# FPC_CAP_Water_Level.net
KiCad netlist of a schematic drawn in Altium Designer
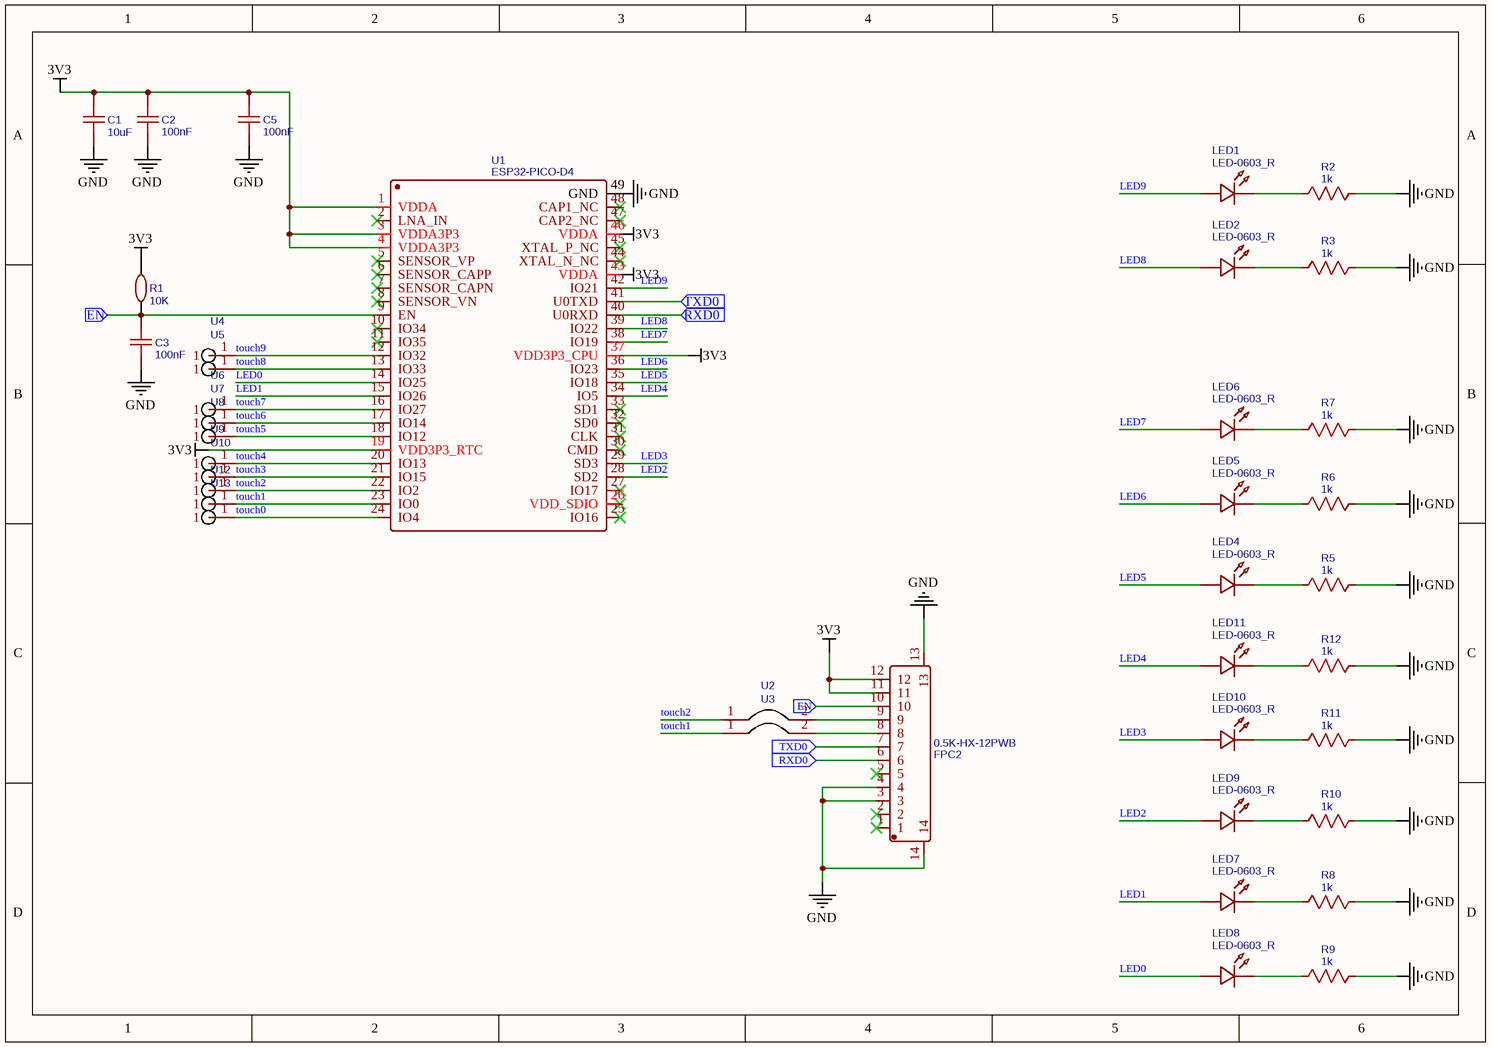
[diagram p0: FPC_CAP_Water_Level.schdoc]

(export (version "E")
  (design (tool "Eeschema 10.0.6"))
  (components
    (comp (ref "C1")
      (value "10uF")
      (footprint "C0603")
      (fields (field (name "MANUFACTURER") "SAMSUNG") (field (name "MANUFACTURER PART") "CL10A106MP8NNNC"))
      (libsource (lib "altium-import") (part "root_1_10uF_"))
    )
    (comp (ref "C2")
      (value "100nF")
      (footprint "C0603")
      (fields (field (name "MANUFACTURER") "SAMSUNG") (field (name "MANUFACTURER PART") "CL10B104KB8NNNC"))
      (libsource (lib "altium-import") (part "root_1_100nF_"))
    )
    (comp (ref "C3")
      (value "100nF")
      (footprint "C0603")
      (fields (field (name "MANUFACTURER") "SAMSUNG") (field (name "MANUFACTURER PART") "CL10B104KB8NNNC"))
      (libsource (lib "altium-import") (part "root_1_100nF_"))
    )
    (comp (ref "C5")
      (value "100nF")
      (footprint "C0603")
      (fields (field (name "MANUFACTURER") "SAMSUNG") (field (name "MANUFACTURER PART") "CL10B104KB8NNNC"))
      (libsource (lib "altium-import") (part "root_1_100nF_"))
    )
    (comp (ref "FPC2")
      (value "0.5K-HX-12PWB")
      (footprint "FPC-SMD_12P-P0.50_HDGC_0.5K-HX-12PWB")
      (fields (field (name "MANUFACTURER") "HDGC(华德共创)") (field (name "CONTRIBUTOR") "LCSC"))
      (libsource (lib "altium-import") (part "root_0_0.5K-HX-12PWB_"))
    )
    (comp (ref "LED1")
      (value "LED-0603_R")
      (footprint "LED0603_RED")
      (fields
        (field (name "MANUFACTURER") "EVERLIGHT(台湾亿光)")
        (field (name "MANUFACTURER PART") "19-217/R6C-AL1M2VY/3T")
        (field (name "CONTRIBUTOR") "LCEDA_01")
      )
      (libsource (lib "altium-import") (part "root_0_LED-0603_R_"))
    )
    (comp (ref "LED2")
      (value "LED-0603_R")
      (footprint "LED0603_RED")
      (fields
        (field (name "MANUFACTURER") "EVERLIGHT(台湾亿光)")
        (field (name "MANUFACTURER PART") "19-217/R6C-AL1M2VY/3T")
        (field (name "CONTRIBUTOR") "LCEDA_01")
      )
      (libsource (lib "altium-import") (part "root_0_LED-0603_R_"))
    )
    (comp (ref "LED4")
      (value "LED-0603_R")
      (footprint "LED0603_RED")
      (fields
        (field (name "MANUFACTURER") "EVERLIGHT(台湾亿光)")
        (field (name "MANUFACTURER PART") "19-217/R6C-AL1M2VY/3T")
        (field (name "CONTRIBUTOR") "LCEDA_01")
      )
      (libsource (lib "altium-import") (part "root_0_LED-0603_R_"))
    )
    (comp (ref "LED5")
      (value "LED-0603_R")
      (footprint "LED0603_RED")
      (fields
        (field (name "MANUFACTURER") "EVERLIGHT(台湾亿光)")
        (field (name "MANUFACTURER PART") "19-217/R6C-AL1M2VY/3T")
        (field (name "CONTRIBUTOR") "LCEDA_01")
      )
      (libsource (lib "altium-import") (part "root_0_LED-0603_R_"))
    )
    (comp (ref "LED6")
      (value "LED-0603_R")
      (footprint "LED0603_RED")
      (fields
        (field (name "MANUFACTURER") "EVERLIGHT(台湾亿光)")
        (field (name "MANUFACTURER PART") "19-217/R6C-AL1M2VY/3T")
        (field (name "CONTRIBUTOR") "LCEDA_01")
      )
      (libsource (lib "altium-import") (part "root_0_LED-0603_R_"))
    )
    (comp (ref "LED7")
      (value "LED-0603_R")
      (footprint "LED0603_RED")
      (fields
        (field (name "MANUFACTURER") "EVERLIGHT(台湾亿光)")
        (field (name "MANUFACTURER PART") "19-217/R6C-AL1M2VY/3T")
        (field (name "CONTRIBUTOR") "LCEDA_01")
      )
      (libsource (lib "altium-import") (part "root_0_LED-0603_R_"))
    )
    (comp (ref "LED8")
      (value "LED-0603_R")
      (footprint "LED0603_RED")
      (fields
        (field (name "MANUFACTURER") "EVERLIGHT(台湾亿光)")
        (field (name "MANUFACTURER PART") "19-217/R6C-AL1M2VY/3T")
        (field (name "CONTRIBUTOR") "LCEDA_01")
      )
      (libsource (lib "altium-import") (part "root_0_LED-0603_R_"))
    )
    (comp (ref "LED9")
      (value "LED-0603_R")
      (footprint "LED0603_RED")
      (fields
        (field (name "MANUFACTURER") "EVERLIGHT(台湾亿光)")
        (field (name "MANUFACTURER PART") "19-217/R6C-AL1M2VY/3T")
        (field (name "CONTRIBUTOR") "LCEDA_01")
      )
      (libsource (lib "altium-import") (part "root_0_LED-0603_R_"))
    )
    (comp (ref "LED10")
      (value "LED-0603_R")
      (footprint "LED0603_RED")
      (fields
        (field (name "MANUFACTURER") "EVERLIGHT(台湾亿光)")
        (field (name "MANUFACTURER PART") "19-217/R6C-AL1M2VY/3T")
        (field (name "CONTRIBUTOR") "LCEDA_01")
      )
      (libsource (lib "altium-import") (part "root_0_LED-0603_R_"))
    )
    (comp (ref "LED11")
      (value "LED-0603_R")
      (footprint "LED0603_RED")
      (fields
        (field (name "MANUFACTURER") "EVERLIGHT(台湾亿光)")
        (field (name "MANUFACTURER PART") "19-217/R6C-AL1M2VY/3T")
        (field (name "CONTRIBUTOR") "LCEDA_01")
      )
      (libsource (lib "altium-import") (part "root_0_LED-0603_R_"))
    )
    (comp (ref "R1")
      (value "10K")
      (footprint "R0603")
      (fields (field (name "MANUFACTURER") "UniOhm") (field (name "MANUFACTURER PART") "0603WAF1002T5E"))
      (libsource (lib "altium-import") (part "root_1_10K_"))
    )
    (comp (ref "R2")
      (value "1k")
      (footprint "R0603")
      (fields (field (name "CONTRIBUTOR") "LCEDA_Lib"))
      (libsource (lib "altium-import") (part "root_0_1k_"))
    )
    (comp (ref "R3")
      (value "1k")
      (footprint "R0603")
      (fields (field (name "CONTRIBUTOR") "LCEDA_Lib"))
      (libsource (lib "altium-import") (part "root_0_1k_"))
    )
    (comp (ref "R5")
      (value "1k")
      (footprint "R0603")
      (fields (field (name "CONTRIBUTOR") "LCEDA_Lib"))
      (libsource (lib "altium-import") (part "root_0_1k_"))
    )
    (comp (ref "R6")
      (value "1k")
      (footprint "R0603")
      (fields (field (name "CONTRIBUTOR") "LCEDA_Lib"))
      (libsource (lib "altium-import") (part "root_0_1k_"))
    )
    (comp (ref "R7")
      (value "1k")
      (footprint "R0603")
      (fields (field (name "CONTRIBUTOR") "LCEDA_Lib"))
      (libsource (lib "altium-import") (part "root_0_1k_"))
    )
    (comp (ref "R8")
      (value "1k")
      (footprint "R0603")
      (fields (field (name "CONTRIBUTOR") "LCEDA_Lib"))
      (libsource (lib "altium-import") (part "root_0_1k_"))
    )
    (comp (ref "R9")
      (value "1k")
      (footprint "R0603")
      (fields (field (name "CONTRIBUTOR") "LCEDA_Lib"))
      (libsource (lib "altium-import") (part "root_0_1k_"))
    )
    (comp (ref "R10")
      (value "1k")
      (footprint "R0603")
      (fields (field (name "CONTRIBUTOR") "LCEDA_Lib"))
      (libsource (lib "altium-import") (part "root_0_1k_"))
    )
    (comp (ref "R11")
      (value "1k")
      (footprint "R0603")
      (fields (field (name "CONTRIBUTOR") "LCEDA_Lib"))
      (libsource (lib "altium-import") (part "root_0_1k_"))
    )
    (comp (ref "R12")
      (value "1k")
      (footprint "R0603")
      (fields (field (name "CONTRIBUTOR") "LCEDA_Lib"))
      (libsource (lib "altium-import") (part "root_0_1k_"))
    )
    (comp (ref "U1")
      (value "ESP32-PICO-D4")
      (footprint "ESP32 PICO")
      (fields (field (name "MANUFACTURER") "Espressif Systems") (field (name "CONTRIBUTOR") "LCSC"))
      (libsource (lib "altium-import") (part "root_0_ESP32-PICO-D4_"))
    )
    (comp (ref "U2")
      (value "短路点 0603")
      (footprint "短路点")
      (fields (field (name "CONTRIBUTOR") "CYIIOT"))
      (libsource (lib "altium-import") (part "root_0_短路点 0603_"))
    )
    (comp (ref "U3")
      (value "短路点 0603")
      (footprint "短路点")
      (fields (field (name "CONTRIBUTOR") "CYIIOT"))
      (libsource (lib "altium-import") (part "root_0_短路点 0603_"))
    )
    (comp (ref "U4")
      (value "测试点")
      (footprint "测试点")
      (fields (field (name "CONTRIBUTOR") "cnweix"))
      (libsource (lib "altium-import") (part "root_0_测试点_"))
    )
    (comp (ref "U5")
      (value "测试点")
      (footprint "测试点")
      (fields (field (name "CONTRIBUTOR") "cnweix"))
      (libsource (lib "altium-import") (part "root_0_测试点_"))
    )
    (comp (ref "U6")
      (value "测试点")
      (footprint "测试点")
      (fields (field (name "CONTRIBUTOR") "cnweix"))
      (libsource (lib "altium-import") (part "root_0_测试点_"))
    )
    (comp (ref "U7")
      (value "测试点")
      (footprint "测试点")
      (fields (field (name "CONTRIBUTOR") "cnweix"))
      (libsource (lib "altium-import") (part "root_0_测试点_"))
    )
    (comp (ref "U8")
      (value "测试点")
      (footprint "测试点")
      (fields (field (name "CONTRIBUTOR") "cnweix"))
      (libsource (lib "altium-import") (part "root_0_测试点_"))
    )
    (comp (ref "U9")
      (value "测试点")
      (footprint "测试点")
      (fields (field (name "CONTRIBUTOR") "cnweix"))
      (libsource (lib "altium-import") (part "root_0_测试点_"))
    )
    (comp (ref "U10")
      (value "测试点")
      (footprint "测试点")
      (fields (field (name "CONTRIBUTOR") "cnweix"))
      (libsource (lib "altium-import") (part "root_0_测试点_"))
    )
    (comp (ref "U11")
      (value "测试点")
      (footprint "测试点")
      (fields (field (name "CONTRIBUTOR") "cnweix"))
      (libsource (lib "altium-import") (part "root_0_测试点_"))
    )
    (comp (ref "U12")
      (value "测试点")
      (footprint "测试点")
      (fields (field (name "CONTRIBUTOR") "cnweix"))
      (libsource (lib "altium-import") (part "root_0_测试点_"))
    )
    (comp (ref "U13")
      (value "测试点")
      (footprint "测试点")
      (fields (field (name "CONTRIBUTOR") "cnweix"))
      (libsource (lib "altium-import") (part "root_0_测试点_"))
    )
  )
  (nets
    (net (code "1") (name "/EN") (class "Default")
      (node (ref "C3") (pin "2") (pinfunction "2_2") (pintype "passive"))
      (node (ref "FPC2") (pin "10") (pinfunction "10_10") (pintype "passive"))
      (node (ref "R1") (pin "1") (pinfunction "1_1") (pintype "passive"))
      (node (ref "U1") (pin "9") (pinfunction "EN_9") (pintype "passive"))
    )
    (net (code "2") (name "/LED0") (class "Default")
      (node (ref "LED8") (pin "1") (pinfunction "1_1") (pintype "passive"))
      (node (ref "U1") (pin "14") (pinfunction "IO25_14") (pintype "passive"))
    )
    (net (code "3") (name "/LED1") (class "Default")
      (node (ref "LED7") (pin "1") (pinfunction "1_1") (pintype "passive"))
      (node (ref "U1") (pin "15") (pinfunction "IO26_15") (pintype "passive"))
    )
    (net (code "4") (name "/LED2") (class "Default")
      (node (ref "LED9") (pin "1") (pinfunction "1_1") (pintype "passive"))
      (node (ref "U1") (pin "28") (pinfunction "SD2_28") (pintype "passive"))
    )
    (net (code "5") (name "/LED3") (class "Default")
      (node (ref "LED10") (pin "1") (pinfunction "1_1") (pintype "passive"))
      (node (ref "U1") (pin "29") (pinfunction "SD3_29") (pintype "passive"))
    )
    (net (code "6") (name "/LED4") (class "Default")
      (node (ref "LED11") (pin "1") (pinfunction "1_1") (pintype "passive"))
      (node (ref "U1") (pin "34") (pinfunction "IO5_34") (pintype "passive"))
    )
    (net (code "7") (name "/LED5") (class "Default")
      (node (ref "LED4") (pin "1") (pinfunction "1_1") (pintype "passive"))
      (node (ref "U1") (pin "35") (pinfunction "IO18_35") (pintype "passive"))
    )
    (net (code "8") (name "/LED6") (class "Default")
      (node (ref "LED5") (pin "1") (pinfunction "1_1") (pintype "passive"))
      (node (ref "U1") (pin "36") (pinfunction "IO23_36") (pintype "passive"))
    )
    (net (code "9") (name "/LED7") (class "Default")
      (node (ref "LED6") (pin "1") (pinfunction "1_1") (pintype "passive"))
      (node (ref "U1") (pin "38") (pinfunction "IO19_38") (pintype "passive"))
    )
    (net (code "10") (name "/LED8") (class "Default")
      (node (ref "LED2") (pin "1") (pinfunction "1_1") (pintype "passive"))
      (node (ref "U1") (pin "39") (pinfunction "IO22_39") (pintype "passive"))
    )
    (net (code "11") (name "/LED9") (class "Default")
      (node (ref "LED1") (pin "1") (pinfunction "1_1") (pintype "passive"))
      (node (ref "U1") (pin "42") (pinfunction "IO21_42") (pintype "passive"))
    )
    (net (code "12") (name "/RXD0") (class "Default")
      (node (ref "FPC2") (pin "6") (pinfunction "6_6") (pintype "passive"))
      (node (ref "U1") (pin "40") (pinfunction "U0RXD_40") (pintype "passive"))
    )
    (net (code "13") (name "/TXD0") (class "Default")
      (node (ref "FPC2") (pin "7") (pinfunction "7_7") (pintype "passive"))
      (node (ref "U1") (pin "41") (pinfunction "U0TXD_41") (pintype "passive"))
    )
    (net (code "14") (name "/touch0") (class "Default")
      (node (ref "U1") (pin "24") (pinfunction "IO4_24") (pintype "passive"))
      (node (ref "U13") (pin "1") (pinfunction "1_1") (pintype "passive"))
    )
    (net (code "15") (name "/touch1") (class "Default")
      (node (ref "U1") (pin "23") (pinfunction "IO0_23") (pintype "passive"))
      (node (ref "U12") (pin "1") (pinfunction "1_1") (pintype "passive"))
      (node (ref "U3") (pin "1") (pinfunction "1_1") (pintype "passive"))
    )
    (net (code "16") (name "/touch2") (class "Default")
      (node (ref "U1") (pin "22") (pinfunction "IO2_22") (pintype "passive"))
      (node (ref "U11") (pin "1") (pinfunction "1_1") (pintype "passive"))
      (node (ref "U2") (pin "1") (pinfunction "1_1") (pintype "passive"))
    )
    (net (code "17") (name "/touch3") (class "Default")
      (node (ref "U1") (pin "21") (pinfunction "IO15_21") (pintype "passive"))
      (node (ref "U10") (pin "1") (pinfunction "1_1") (pintype "passive"))
    )
    (net (code "18") (name "/touch4") (class "Default")
      (node (ref "U1") (pin "20") (pinfunction "IO13_20") (pintype "passive"))
      (node (ref "U9") (pin "1") (pinfunction "1_1") (pintype "passive"))
    )
    (net (code "19") (name "/touch5") (class "Default")
      (node (ref "U1") (pin "18") (pinfunction "IO12_18") (pintype "passive"))
      (node (ref "U8") (pin "1") (pinfunction "1_1") (pintype "passive"))
    )
    (net (code "20") (name "/touch6") (class "Default")
      (node (ref "U1") (pin "17") (pinfunction "IO14_17") (pintype "passive"))
      (node (ref "U7") (pin "1") (pinfunction "1_1") (pintype "passive"))
    )
    (net (code "21") (name "/touch7") (class "Default")
      (node (ref "U1") (pin "16") (pinfunction "IO27_16") (pintype "passive"))
      (node (ref "U6") (pin "1") (pinfunction "1_1") (pintype "passive"))
    )
    (net (code "22") (name "/touch8") (class "Default")
      (node (ref "U1") (pin "13") (pinfunction "IO33_13") (pintype "passive"))
      (node (ref "U5") (pin "1") (pinfunction "1_1") (pintype "passive"))
    )
    (net (code "23") (name "/touch9") (class "Default")
      (node (ref "U1") (pin "12") (pinfunction "IO32_12") (pintype "passive"))
      (node (ref "U4") (pin "1") (pinfunction "1_1") (pintype "passive"))
    )
    (net (code "24") (name "3V3") (class "Default")
      (node (ref "C1") (pin "2") (pinfunction "2_2") (pintype "passive"))
      (node (ref "C2") (pin "2") (pinfunction "2_2") (pintype "passive"))
      (node (ref "C5") (pin "2") (pinfunction "2_2") (pintype "passive"))
      (node (ref "FPC2") (pin "11") (pinfunction "11_11") (pintype "passive"))
      (node (ref "FPC2") (pin "12") (pinfunction "12_12") (pintype "passive"))
      (node (ref "R1") (pin "2") (pinfunction "2_2") (pintype "passive"))
      (node (ref "U1") (pin "1") (pinfunction "VDDA_1") (pintype "passive"))
      (node (ref "U1") (pin "19") (pinfunction "VDD3P3_RTC_19") (pintype "passive"))
      (node (ref "U1") (pin "3") (pinfunction "VDDA3P3_3") (pintype "passive"))
      (node (ref "U1") (pin "37") (pinfunction "VDD3P3_CPU_37") (pintype "passive"))
      (node (ref "U1") (pin "4") (pinfunction "VDDA3P3_4") (pintype "passive"))
      (node (ref "U1") (pin "43") (pinfunction "VDDA_43") (pintype "passive"))
      (node (ref "U1") (pin "46") (pinfunction "VDDA_46") (pintype "passive"))
    )
    (net (code "25") (name "GND") (class "Default")
      (node (ref "C1") (pin "1") (pinfunction "1_1") (pintype "passive"))
      (node (ref "C2") (pin "1") (pinfunction "1_1") (pintype "passive"))
      (node (ref "C3") (pin "1") (pinfunction "1_1") (pintype "passive"))
      (node (ref "C5") (pin "1") (pinfunction "1_1") (pintype "passive"))
      (node (ref "FPC2") (pin "13") (pinfunction "13_13") (pintype "passive"))
      (node (ref "FPC2") (pin "14") (pinfunction "14_14") (pintype "passive"))
      (node (ref "FPC2") (pin "3") (pinfunction "3_3") (pintype "passive"))
      (node (ref "FPC2") (pin "4") (pinfunction "4_4") (pintype "passive"))
      (node (ref "R10") (pin "2") (pinfunction "2_2") (pintype "passive"))
      (node (ref "R11") (pin "2") (pinfunction "2_2") (pintype "passive"))
      (node (ref "R12") (pin "2") (pinfunction "2_2") (pintype "passive"))
      (node (ref "R2") (pin "2") (pinfunction "2_2") (pintype "passive"))
      (node (ref "R3") (pin "2") (pinfunction "2_2") (pintype "passive"))
      (node (ref "R5") (pin "2") (pinfunction "2_2") (pintype "passive"))
      (node (ref "R6") (pin "2") (pinfunction "2_2") (pintype "passive"))
      (node (ref "R7") (pin "2") (pinfunction "2_2") (pintype "passive"))
      (node (ref "R8") (pin "2") (pinfunction "2_2") (pintype "passive"))
      (node (ref "R9") (pin "2") (pinfunction "2_2") (pintype "passive"))
      (node (ref "U1") (pin "49") (pinfunction "GND_49") (pintype "passive"))
    )
    (net (code "26") (name "Net-(FPC2-Pad8)") (class "Default")
      (node (ref "FPC2") (pin "8") (pinfunction "8_8") (pintype "passive"))
      (node (ref "U3") (pin "2") (pinfunction "2_2") (pintype "passive"))
    )
    (net (code "27") (name "Net-(FPC2-Pad9)") (class "Default")
      (node (ref "FPC2") (pin "9") (pinfunction "9_9") (pintype "passive"))
      (node (ref "U2") (pin "2") (pinfunction "2_2") (pintype "passive"))
    )
    (net (code "28") (name "Net-(LED1-Pad2)") (class "Default")
      (node (ref "LED1") (pin "2") (pinfunction "2_2") (pintype "passive"))
      (node (ref "R2") (pin "1") (pinfunction "1_1") (pintype "passive"))
    )
    (net (code "29") (name "Net-(LED2-Pad2)") (class "Default")
      (node (ref "LED2") (pin "2") (pinfunction "2_2") (pintype "passive"))
      (node (ref "R3") (pin "1") (pinfunction "1_1") (pintype "passive"))
    )
    (net (code "30") (name "Net-(LED4-Pad2)") (class "Default")
      (node (ref "LED4") (pin "2") (pinfunction "2_2") (pintype "passive"))
      (node (ref "R5") (pin "1") (pinfunction "1_1") (pintype "passive"))
    )
    (net (code "31") (name "Net-(LED5-Pad2)") (class "Default")
      (node (ref "LED5") (pin "2") (pinfunction "2_2") (pintype "passive"))
      (node (ref "R6") (pin "1") (pinfunction "1_1") (pintype "passive"))
    )
    (net (code "32") (name "Net-(LED6-Pad2)") (class "Default")
      (node (ref "LED6") (pin "2") (pinfunction "2_2") (pintype "passive"))
      (node (ref "R7") (pin "1") (pinfunction "1_1") (pintype "passive"))
    )
    (net (code "33") (name "Net-(LED7-Pad2)") (class "Default")
      (node (ref "LED7") (pin "2") (pinfunction "2_2") (pintype "passive"))
      (node (ref "R8") (pin "1") (pinfunction "1_1") (pintype "passive"))
    )
    (net (code "34") (name "Net-(LED8-Pad2)") (class "Default")
      (node (ref "LED8") (pin "2") (pinfunction "2_2") (pintype "passive"))
      (node (ref "R9") (pin "1") (pinfunction "1_1") (pintype "passive"))
    )
    (net (code "35") (name "Net-(LED9-Pad2)") (class "Default")
      (node (ref "LED9") (pin "2") (pinfunction "2_2") (pintype "passive"))
      (node (ref "R10") (pin "1") (pinfunction "1_1") (pintype "passive"))
    )
    (net (code "36") (name "Net-(LED10-Pad2)") (class "Default")
      (node (ref "LED10") (pin "2") (pinfunction "2_2") (pintype "passive"))
      (node (ref "R11") (pin "1") (pinfunction "1_1") (pintype "passive"))
    )
    (net (code "37") (name "Net-(LED11-Pad2)") (class "Default")
      (node (ref "LED11") (pin "2") (pinfunction "2_2") (pintype "passive"))
      (node (ref "R12") (pin "1") (pinfunction "1_1") (pintype "passive"))
    )
    (net (code "38") (name "unconnected-(FPC2-Pad1)") (class "Default")
      (node (ref "FPC2") (pin "1") (pinfunction "1_1") (pintype "passive+no_connect"))
    )
    (net (code "39") (name "unconnected-(FPC2-Pad2)") (class "Default")
      (node (ref "FPC2") (pin "2") (pinfunction "2_2") (pintype "passive+no_connect"))
    )
    (net (code "40") (name "unconnected-(FPC2-Pad5)") (class "Default")
      (node (ref "FPC2") (pin "5") (pinfunction "5_5") (pintype "passive+no_connect"))
    )
    (net (code "41") (name "unconnected-(U1-CAP1_NC-Pad48)") (class "Default")
      (node (ref "U1") (pin "48") (pinfunction "CAP1_NC_48") (pintype "passive+no_connect"))
    )
    (net (code "42") (name "unconnected-(U1-CAP2_NC-Pad47)") (class "Default")
      (node (ref "U1") (pin "47") (pinfunction "CAP2_NC_47") (pintype "passive+no_connect"))
    )
    (net (code "43") (name "unconnected-(U1-CLK-Pad31)") (class "Default")
      (node (ref "U1") (pin "31") (pinfunction "CLK_31") (pintype "passive+no_connect"))
    )
    (net (code "44") (name "unconnected-(U1-CMD-Pad30)") (class "Default")
      (node (ref "U1") (pin "30") (pinfunction "CMD_30") (pintype "passive+no_connect"))
    )
    (net (code "45") (name "unconnected-(U1-IO16-Pad25)") (class "Default")
      (node (ref "U1") (pin "25") (pinfunction "IO16_25") (pintype "passive+no_connect"))
    )
    (net (code "46") (name "unconnected-(U1-IO17-Pad27)") (class "Default")
      (node (ref "U1") (pin "27") (pinfunction "IO17_27") (pintype "passive+no_connect"))
    )
    (net (code "47") (name "unconnected-(U1-IO34-Pad10)") (class "Default")
      (node (ref "U1") (pin "10") (pinfunction "IO34_10") (pintype "passive+no_connect"))
    )
    (net (code "48") (name "unconnected-(U1-IO35-Pad11)") (class "Default")
      (node (ref "U1") (pin "11") (pinfunction "IO35_11") (pintype "passive+no_connect"))
    )
    (net (code "49") (name "unconnected-(U1-LNA_IN-Pad2)") (class "Default")
      (node (ref "U1") (pin "2") (pinfunction "LNA_IN_2") (pintype "passive+no_connect"))
    )
    (net (code "50") (name "unconnected-(U1-SD0-Pad32)") (class "Default")
      (node (ref "U1") (pin "32") (pinfunction "SD0_32") (pintype "passive+no_connect"))
    )
    (net (code "51") (name "unconnected-(U1-SD1-Pad33)") (class "Default")
      (node (ref "U1") (pin "33") (pinfunction "SD1_33") (pintype "passive+no_connect"))
    )
    (net (code "52") (name "unconnected-(U1-SENSOR_CAPN-Pad7)") (class "Default")
      (node (ref "U1") (pin "7") (pinfunction "SENSOR_CAPN_7") (pintype "passive+no_connect"))
    )
    (net (code "53") (name "unconnected-(U1-SENSOR_CAPP-Pad6)") (class "Default")
      (node (ref "U1") (pin "6") (pinfunction "SENSOR_CAPP_6") (pintype "passive+no_connect"))
    )
    (net (code "54") (name "unconnected-(U1-SENSOR_VN-Pad8)") (class "Default")
      (node (ref "U1") (pin "8") (pinfunction "SENSOR_VN_8") (pintype "passive+no_connect"))
    )
    (net (code "55") (name "unconnected-(U1-SENSOR_VP-Pad5)") (class "Default")
      (node (ref "U1") (pin "5") (pinfunction "SENSOR_VP_5") (pintype "passive+no_connect"))
    )
    (net (code "56") (name "unconnected-(U1-VDD_SDIO-Pad26)") (class "Default")
      (node (ref "U1") (pin "26") (pinfunction "VDD_SDIO_26") (pintype "passive+no_connect"))
    )
    (net (code "57") (name "unconnected-(U1-XTAL_N_NC-Pad44)") (class "Default")
      (node (ref "U1") (pin "44") (pinfunction "XTAL_N_NC_44") (pintype "passive+no_connect"))
    )
    (net (code "58") (name "unconnected-(U1-XTAL_P_NC-Pad45)") (class "Default")
      (node (ref "U1") (pin "45") (pinfunction "XTAL_P_NC_45") (pintype "passive+no_connect"))
    )
  )
)
